# Qwiic_ADC_ADS1015.net
KiCad netlist of a schematic drawn in EAGLE
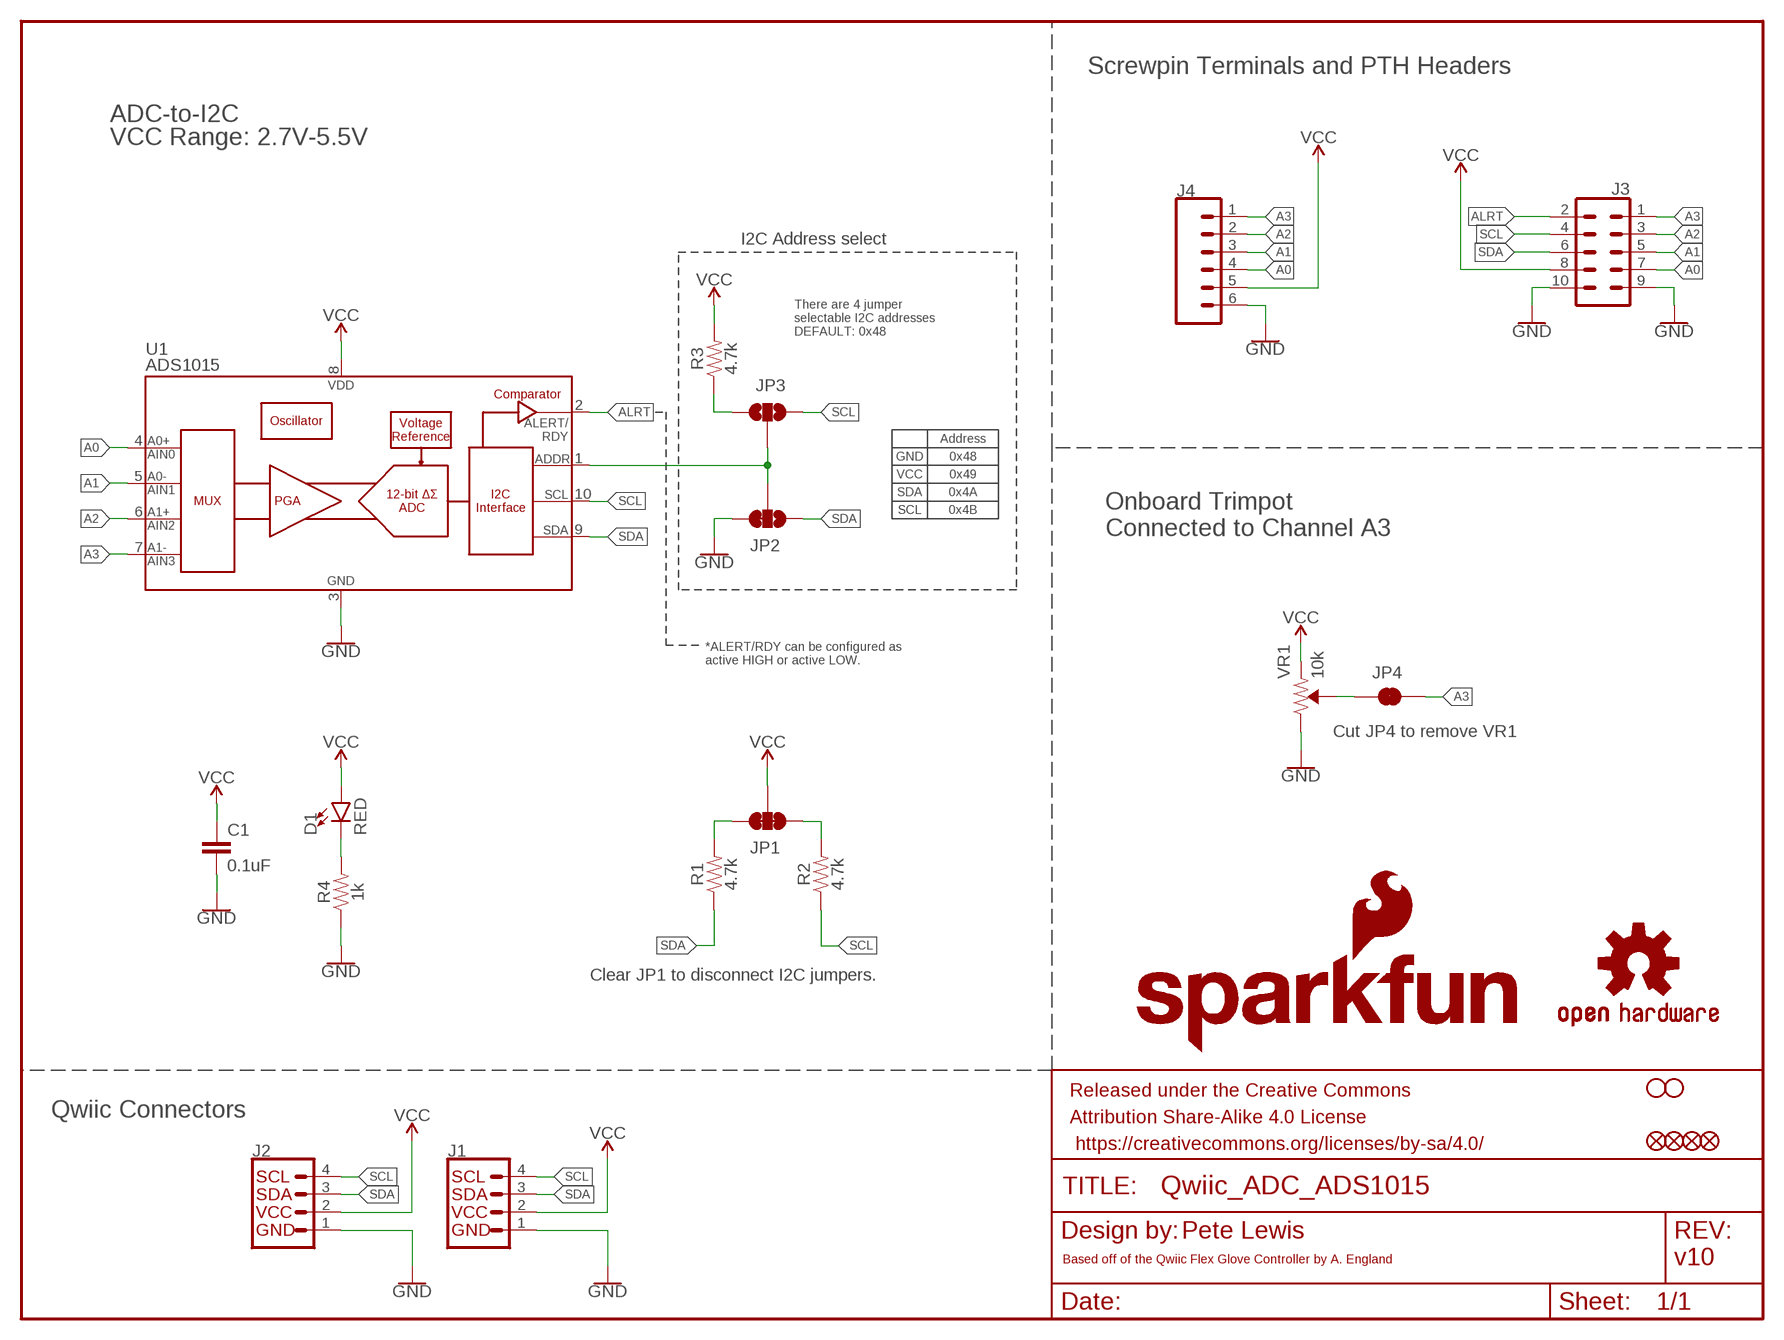
[diagram p0: schematic, sheet 1]

(export (version "E")
  (design (tool "Eeschema 10.0.6"))
  (components
    (comp (ref "C1")
      (value "0.1uF")
      (footprint "eagle-import:0603")
      (libsource (lib "eagle-import") (part "0.1UF-0603-25V-(+80/-20%)"))
    )
    (comp (ref "D1")
      (value "RED")
      (footprint "eagle-import:LED-0603")
      (libsource (lib "eagle-import") (part "LED-RED0603"))
    )
    (comp (ref "FD1")
      (value "FIDUCIALUFIDUCIAL")
      (footprint "eagle-import:FIDUCIAL-MICRO")
      (libsource (lib "eagle-import") (part "FIDUCIALUFIDUCIAL"))
    )
    (comp (ref "FD2")
      (value "FIDUCIALUFIDUCIAL")
      (footprint "eagle-import:FIDUCIAL-MICRO")
      (libsource (lib "eagle-import") (part "FIDUCIALUFIDUCIAL"))
    )
    (comp (ref "FD3")
      (value "FIDUCIALUFIDUCIAL")
      (footprint "eagle-import:FIDUCIAL-MICRO")
      (libsource (lib "eagle-import") (part "FIDUCIALUFIDUCIAL"))
    )
    (comp (ref "FD4")
      (value "FIDUCIALUFIDUCIAL")
      (footprint "eagle-import:FIDUCIAL-MICRO")
      (libsource (lib "eagle-import") (part "FIDUCIALUFIDUCIAL"))
    )
    (comp (ref "FRAME1")
      (value "FRAME-LETTER")
      (footprint "eagle-import:CREATIVE_COMMONS")
      (libsource (lib "eagle-import") (part "FRAME-LETTER"))
    )
    (comp (ref "H1")
      (value "STAND-OFF")
      (footprint "eagle-import:STAND-OFF")
      (libsource (lib "eagle-import") (part "STAND-OFF"))
    )
    (comp (ref "H2")
      (value "STAND-OFF")
      (footprint "eagle-import:STAND-OFF")
      (libsource (lib "eagle-import") (part "STAND-OFF"))
    )
    (comp (ref "J1")
      (value "QWIIC_CONNECTORJS-1MM")
      (footprint "eagle-import:JST04_1MM_RA")
      (libsource (lib "eagle-import") (part "QWIIC_CONNECTORJS-1MM"))
    )
    (comp (ref "J2")
      (value "QWIIC_CONNECTORJS-1MM")
      (footprint "eagle-import:JST04_1MM_RA")
      (libsource (lib "eagle-import") (part "QWIIC_CONNECTORJS-1MM"))
    )
    (comp (ref "J3")
      (value "CONN_05X2NO_SILK")
      (footprint "eagle-import:2X5_NOSILK")
      (libsource (lib "eagle-import") (part "CONN_05X2NO_SILK"))
    )
    (comp (ref "J4")
      (value "Screw Pin")
      (footprint "eagle-import:SCREWTERMINAL-3.5MM-6")
      (libsource (lib "eagle-import") (part "CONN_063.5MM-6"))
    )
    (comp (ref "JP1")
      (value "JUMPER-SMT_3_2-NC_TRACE_NO-SILK")
      (footprint "eagle-import:SMT-JUMPER_3_2-NC_TRACE_NO-SILK")
      (libsource (lib "eagle-import") (part "JUMPER-SMT_3_2-NC_TRACE_NO-SILK"))
    )
    (comp (ref "JP2")
      (value "JUMPER-SMT_3_1-NC_TRACE_NO-SILK")
      (footprint "eagle-import:SMT-JUMPER_3_1-NC_TRACE_NO-SILK")
      (libsource (lib "eagle-import") (part "JUMPER-SMT_3_1-NC_TRACE_NO-SILK"))
    )
    (comp (ref "JP3")
      (value "JUMPER-SMT_3_NO_NO_SILK")
      (footprint "eagle-import:SMT-JUMPER_3_0-NO_TRACE_NO-SILK")
      (libsource (lib "eagle-import") (part "JUMPER-SMT_3_NO_NO_SILK"))
    )
    (comp (ref "JP4")
      (value "JUMPER-SMT_2_NC_TRACE_SILK")
      (footprint "eagle-import:SMT-JUMPER_2_NC_TRACE_SILK")
      (libsource (lib "eagle-import") (part "JUMPER-SMT_2_NC_TRACE_SILK"))
    )
    (comp (ref "LOGO1")
      (value "SFE_LOGO_NAME.1_INCH")
      (footprint "eagle-import:SFE_LOGO_NAME_.1")
      (libsource (lib "eagle-import") (part "SFE_LOGO_NAME.1_INCH"))
    )
    (comp (ref "LOGO2")
      (value "OSHW-LOGOS")
      (footprint "eagle-import:OSHW-LOGO-S")
      (libsource (lib "eagle-import") (part "OSHW-LOGOS"))
    )
    (comp (ref "LOGO3")
      (value "SFE_LOGO_FLAME.1_INCH")
      (footprint "eagle-import:SFE_LOGO_FLAME_.1")
      (libsource (lib "eagle-import") (part "SFE_LOGO_FLAME.1_INCH"))
    )
    (comp (ref "R1")
      (value "4.7k")
      (footprint "eagle-import:0603")
      (libsource (lib "eagle-import") (part "4.7KOHM-0603-1/10W-1%"))
    )
    (comp (ref "R2")
      (value "4.7k")
      (footprint "eagle-import:0603")
      (libsource (lib "eagle-import") (part "4.7KOHM-0603-1/10W-1%"))
    )
    (comp (ref "R3")
      (value "4.7k")
      (footprint "eagle-import:0603")
      (libsource (lib "eagle-import") (part "4.7KOHM-0603-1/10W-1%"))
    )
    (comp (ref "R4")
      (value "1k")
      (footprint "eagle-import:0603")
      (libsource (lib "eagle-import") (part "1KOHM-0603-1/10W-1%"))
    )
    (comp (ref "U1")
      (value "ADS1015")
      (footprint "eagle-import:MSOP10")
      (libsource (lib "eagle-import") (part "ADS1015"))
    )
    (comp (ref "VR1")
      (value "10k")
      (footprint "eagle-import:TRIMPOT-SMD-3MM-CLOSED")
      (libsource (lib "eagle-import") (part "TRIMPOT-SMD-3MM-CLOSED-1/8W-20%"))
    )
  )
  (nets
    (net (code "1") (name "A0") (class "Default")
      (node (ref "J3") (pin "7") (pinfunction "7_7") (pintype "passive"))
      (node (ref "J4") (pin "4") (pinfunction "4_4") (pintype "passive"))
      (node (ref "U1") (pin "4") (pinfunction "AIN0_4") (pintype "bidirectional"))
    )
    (net (code "2") (name "A1") (class "Default")
      (node (ref "J3") (pin "5") (pinfunction "5_5") (pintype "passive"))
      (node (ref "J4") (pin "3") (pinfunction "3_3") (pintype "passive"))
      (node (ref "U1") (pin "5") (pinfunction "AIN1_5") (pintype "bidirectional"))
    )
    (net (code "3") (name "A2") (class "Default")
      (node (ref "J3") (pin "3") (pinfunction "3_3") (pintype "passive"))
      (node (ref "J4") (pin "2") (pinfunction "2_2") (pintype "passive"))
      (node (ref "U1") (pin "6") (pinfunction "AIN2_6") (pintype "bidirectional"))
    )
    (net (code "4") (name "A3") (class "Default")
      (node (ref "J3") (pin "1") (pinfunction "1_1") (pintype "passive"))
      (node (ref "J4") (pin "1") (pinfunction "1_1") (pintype "passive"))
      (node (ref "JP4") (pin "2") (pinfunction "2_2") (pintype "passive"))
      (node (ref "U1") (pin "7") (pinfunction "AIN3_7") (pintype "bidirectional"))
    )
    (net (code "5") (name "ALRT") (class "Default")
      (node (ref "J3") (pin "2") (pinfunction "2_2") (pintype "passive"))
      (node (ref "U1") (pin "2") (pinfunction "ALERT/RDY_2") (pintype "bidirectional"))
    )
    (net (code "6") (name "GND") (class "Default")
      (node (ref "C1") (pin "2") (pinfunction "2_2") (pintype "passive"))
      (node (ref "J1") (pin "1") (pinfunction "1_1") (pintype "power_in"))
      (node (ref "J2") (pin "1") (pinfunction "1_1") (pintype "power_in"))
      (node (ref "J3") (pin "10") (pinfunction "10_10") (pintype "passive"))
      (node (ref "J3") (pin "9") (pinfunction "9_9") (pintype "passive"))
      (node (ref "J4") (pin "6") (pinfunction "6_6") (pintype "passive"))
      (node (ref "JP2") (pin "3") (pinfunction "3_3") (pintype "passive"))
      (node (ref "R4") (pin "1") (pinfunction "1_1") (pintype "passive"))
      (node (ref "U1") (pin "3") (pinfunction "VSS_3") (pintype "bidirectional"))
      (node (ref "VR1") (pin "3") (pinfunction "CW_3") (pintype "passive"))
    )
    (net (code "7") (name "Net-(D1-PadC)") (class "Default")
      (node (ref "D1") (pin "C") (pinfunction "C_C") (pintype "passive"))
      (node (ref "R4") (pin "2") (pinfunction "2_2") (pintype "passive"))
    )
    (net (code "8") (name "Net-(JP1-Pad1)") (class "Default")
      (node (ref "JP1") (pin "1") (pinfunction "1_1") (pintype "passive"))
      (node (ref "R2") (pin "2") (pinfunction "2_2") (pintype "passive"))
    )
    (net (code "9") (name "Net-(JP1-Pad3)") (class "Default")
      (node (ref "JP1") (pin "3") (pinfunction "3_3") (pintype "passive"))
      (node (ref "R1") (pin "2") (pinfunction "2_2") (pintype "passive"))
    )
    (net (code "10") (name "Net-(JP3-Pad1)") (class "Default")
      (node (ref "JP3") (pin "1") (pinfunction "1_1") (pintype "passive"))
      (node (ref "R3") (pin "1") (pinfunction "1_1") (pintype "passive"))
    )
    (net (code "11") (name "Net-(U1-ADDR)") (class "Default")
      (node (ref "JP2") (pin "2") (pinfunction "2_2") (pintype "passive"))
      (node (ref "JP3") (pin "2") (pinfunction "2_2") (pintype "passive"))
      (node (ref "U1") (pin "1") (pinfunction "ADDR_1") (pintype "bidirectional"))
    )
    (net (code "12") (name "Net-(VR1-WIPER)") (class "Default")
      (node (ref "JP4") (pin "1") (pinfunction "1_1") (pintype "passive"))
      (node (ref "VR1") (pin "2") (pinfunction "WIPER_2") (pintype "passive"))
    )
    (net (code "13") (name "SCL") (class "Default")
      (node (ref "J1") (pin "4") (pinfunction "4_4") (pintype "passive"))
      (node (ref "J2") (pin "4") (pinfunction "4_4") (pintype "passive"))
      (node (ref "J3") (pin "4") (pinfunction "4_4") (pintype "passive"))
      (node (ref "JP3") (pin "3") (pinfunction "3_3") (pintype "passive"))
      (node (ref "R2") (pin "1") (pinfunction "1_1") (pintype "passive"))
      (node (ref "U1") (pin "10") (pinfunction "SCL_10") (pintype "bidirectional"))
    )
    (net (code "14") (name "SDA") (class "Default")
      (node (ref "J1") (pin "3") (pinfunction "3_3") (pintype "passive"))
      (node (ref "J2") (pin "3") (pinfunction "3_3") (pintype "passive"))
      (node (ref "J3") (pin "6") (pinfunction "6_6") (pintype "passive"))
      (node (ref "JP2") (pin "1") (pinfunction "1_1") (pintype "passive"))
      (node (ref "R1") (pin "1") (pinfunction "1_1") (pintype "passive"))
      (node (ref "U1") (pin "9") (pinfunction "SDA_9") (pintype "bidirectional"))
    )
    (net (code "15") (name "VCC") (class "Default")
      (node (ref "C1") (pin "1") (pinfunction "1_1") (pintype "passive"))
      (node (ref "D1") (pin "A") (pinfunction "A_A") (pintype "passive"))
      (node (ref "J1") (pin "2") (pinfunction "2_2") (pintype "power_in"))
      (node (ref "J2") (pin "2") (pinfunction "2_2") (pintype "power_in"))
      (node (ref "J3") (pin "8") (pinfunction "8_8") (pintype "passive"))
      (node (ref "J4") (pin "5") (pinfunction "5_5") (pintype "passive"))
      (node (ref "JP1") (pin "2") (pinfunction "2_2") (pintype "passive"))
      (node (ref "R3") (pin "2") (pinfunction "2_2") (pintype "passive"))
      (node (ref "U1") (pin "8") (pinfunction "VDD_8") (pintype "bidirectional"))
      (node (ref "VR1") (pin "1") (pinfunction "CCW_1") (pintype "passive"))
    )
  )
)
